# BatteryStackMonitor.net
KiCad netlist of a schematic drawn in Altium Designer
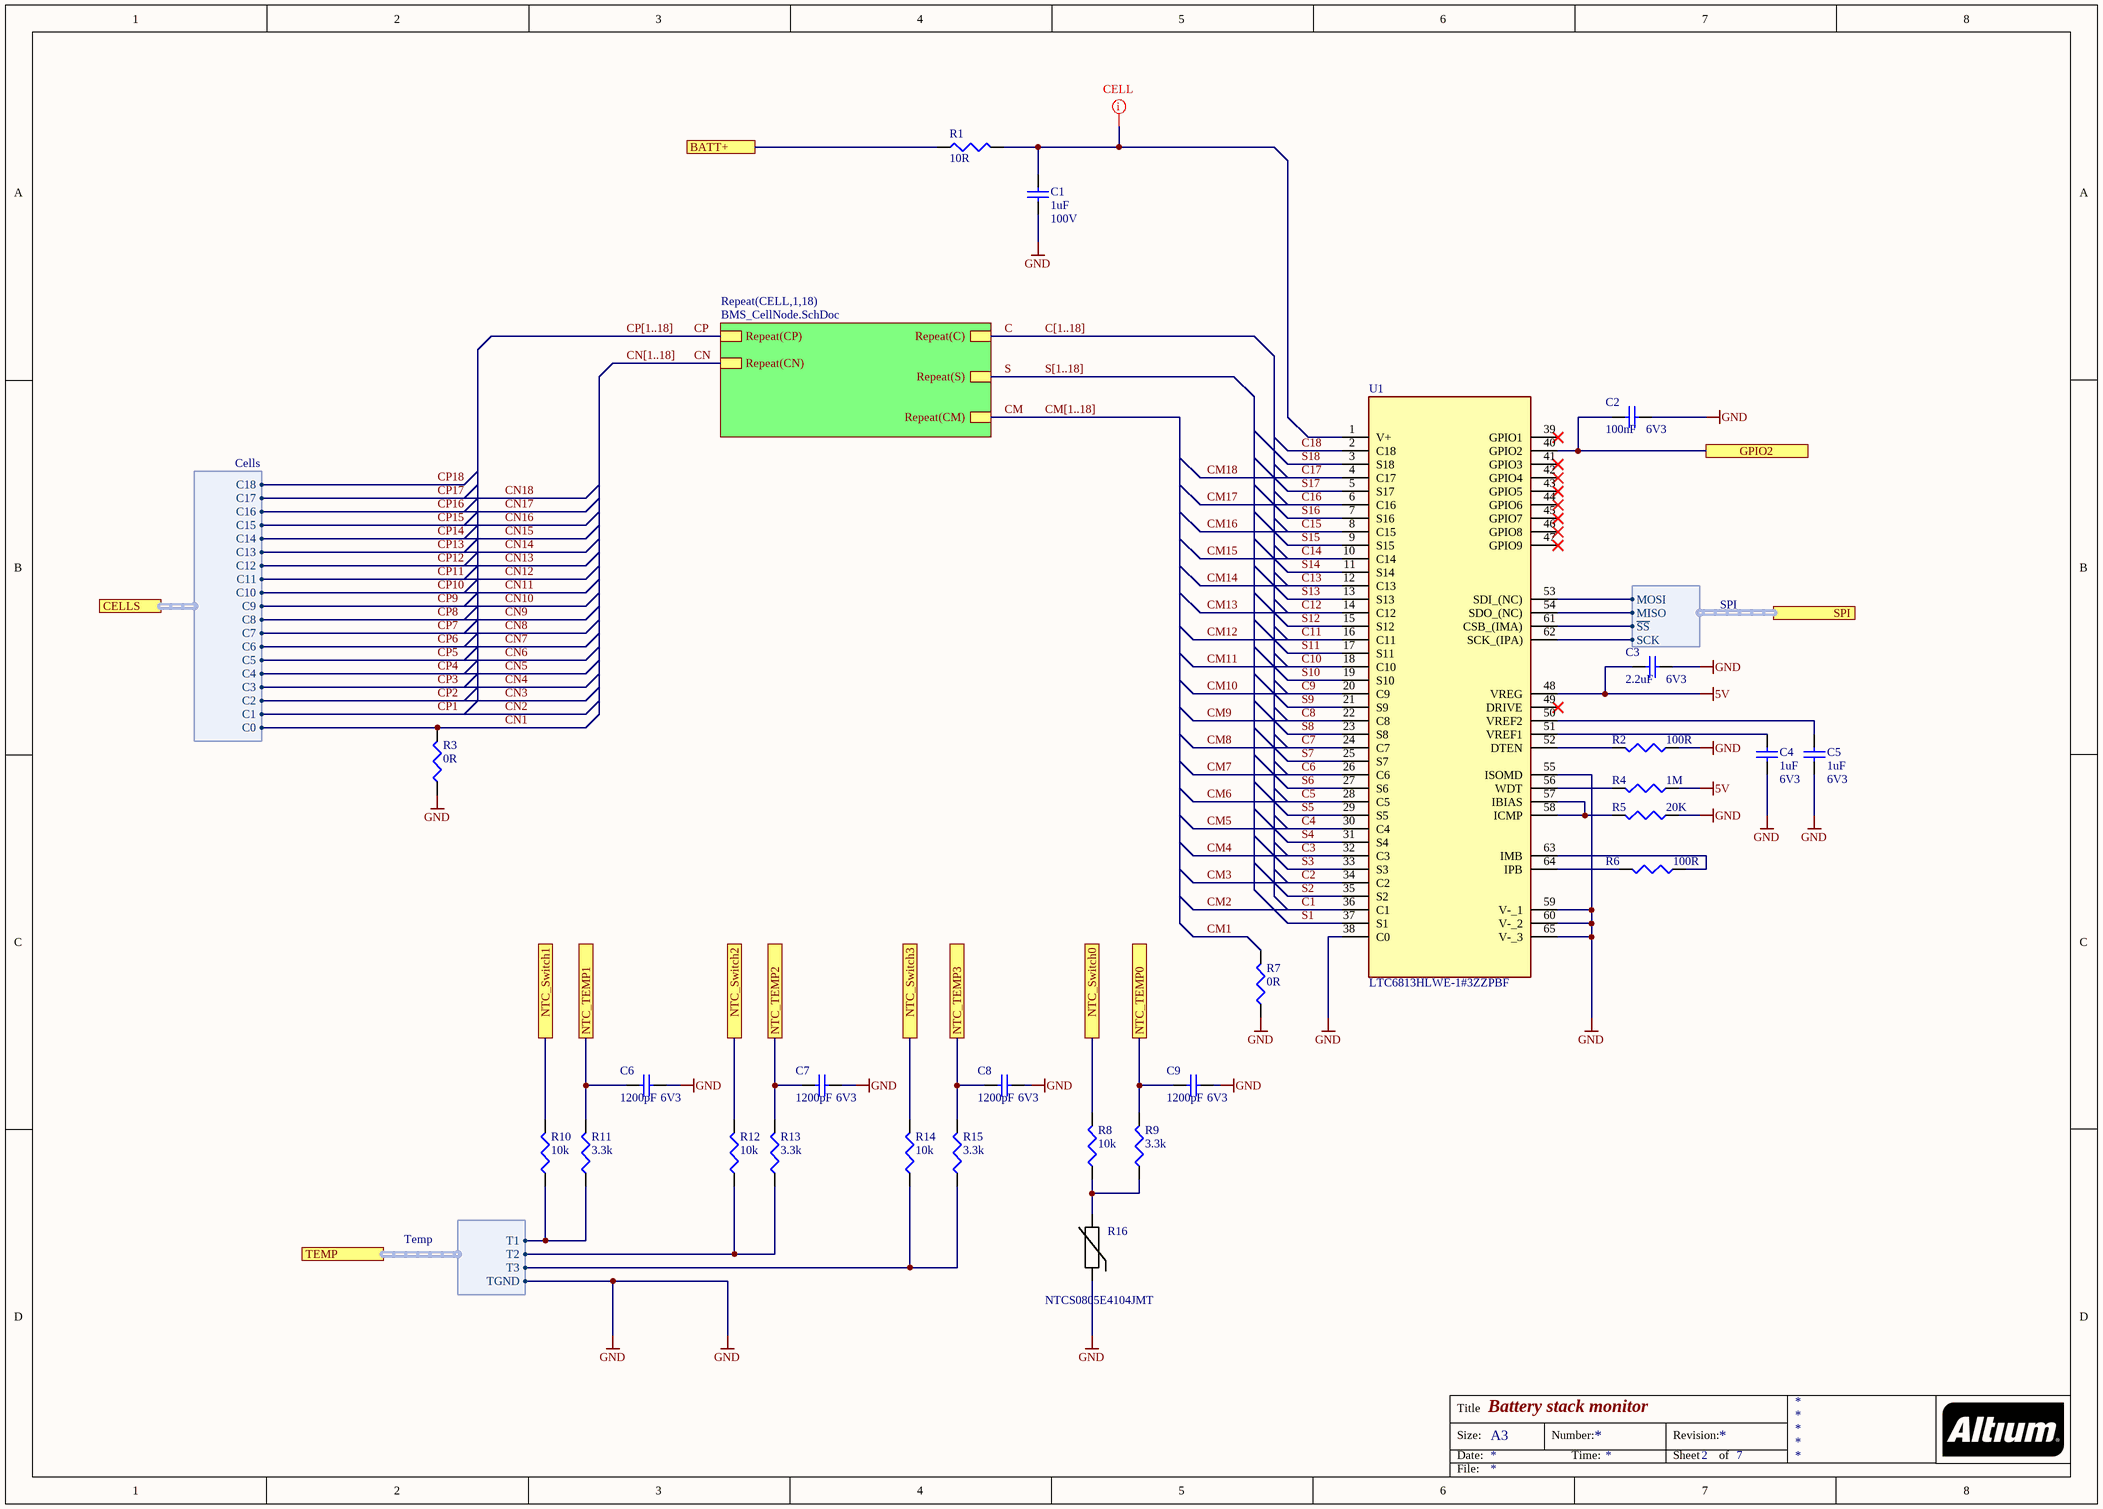
[diagram p0: BatteryStackMonitor.SchDoc]

(export (version "E")
  (design (tool "Eeschema 10.0.6"))
  (components
    (comp (ref "C1")
      (value "1uF")
      (footprint "VESC_BMS:C-1206")
      (description "Capacitor, 1uF, 100V, X7R")
      (fields (field (name "VOLTAGE RATING") "100V"))
      (libsource (lib "AR_Capacitors_Ceramic") (part "1uF/1206/CER/100V"))
    )
    (comp (ref "C2")
      (value "100nF")
      (footprint "VESC_BMS:C0402")
      (description "Capacitor, 1uF, 6.3V, X5R")
      (fields (field (name "VOLTAGE RATING") "6V3"))
      (libsource (lib "AR_Capacitors_Ceramic") (part "1uF/0402/CER/6.3V"))
    )
    (comp (ref "C3")
      (value "2.2uF")
      (footprint "VESC_BMS:C0402")
      (description "Capacitor, 1uF, 6.3V, X5R")
      (fields (field (name "VOLTAGE RATING") "6V3"))
      (libsource (lib "AR_Capacitors_Ceramic") (part "1uF/0402/CER/6.3V"))
    )
    (comp (ref "C4")
      (value "1uF")
      (footprint "VESC_BMS:C0402")
      (description "Capacitor, 1uF, 6.3V, X5R")
      (fields (field (name "VOLTAGE RATING") "6V3"))
      (libsource (lib "AR_Capacitors_Ceramic") (part "1uF/0402/CER/6.3V"))
    )
    (comp (ref "C5")
      (value "1uF")
      (footprint "VESC_BMS:C0402")
      (description "Capacitor, 1uF, 6.3V, X5R")
      (fields (field (name "VOLTAGE RATING") "6V3"))
      (libsource (lib "AR_Capacitors_Ceramic") (part "1uF/0402/CER/6.3V"))
    )
    (comp (ref "C6")
      (value "1200pF")
      (footprint "VESC_BMS:C0402")
      (description "Capacitor, 1uF, 6.3V, X5R")
      (fields (field (name "VOLTAGE RATING") "6V3"))
      (libsource (lib "AR_Capacitors_Ceramic") (part "1uF/0402/CER/6.3V"))
    )
    (comp (ref "C7")
      (value "1200pF")
      (footprint "VESC_BMS:C0402")
      (description "Capacitor, 1uF, 6.3V, X5R")
      (fields (field (name "VOLTAGE RATING") "6V3"))
      (libsource (lib "AR_Capacitors_Ceramic") (part "1uF/0402/CER/6.3V"))
    )
    (comp (ref "C8")
      (value "1200pF")
      (footprint "VESC_BMS:C0402")
      (description "Capacitor, 1uF, 6.3V, X5R")
      (fields (field (name "VOLTAGE RATING") "6V3"))
      (libsource (lib "AR_Capacitors_Ceramic") (part "1uF/0402/CER/6.3V"))
    )
    (comp (ref "C9")
      (value "1200pF")
      (footprint "VESC_BMS:C0402")
      (description "Capacitor, 1uF, 6.3V, X5R")
      (fields (field (name "VOLTAGE RATING") "6V3"))
      (libsource (lib "AR_Capacitors_Ceramic") (part "1uF/0402/CER/6.3V"))
    )
    (comp (ref "R1")
      (value "10R")
      (footprint "R1206")
      (description "Resistor")
      (fields (field (name "MANUFACTURER_PART_NUMBER") "RQ73C2B10RBTDF"))
      (libsource (lib "VESC_BMS") (part "RQ73C2B10RBTDF"))
    )
    (comp (ref "R2")
      (value "100R")
      (footprint "VESC_BMS:0402")
      (description "Resistor, 1M, 0.1%, 0.0625W, 50V, 100PPM, 0402")
      (libsource (lib "AR_Resistors_SMD") (part "1M/0402/0063W/50V"))
    )
    (comp (ref "R3")
      (value "0R")
      (footprint "VESC_BMS:0603")
      (description "Resistor, 0R, 0.1%, 0.063W, 50V, 200PPM, 0603")
      (libsource (lib "AR_Resistors_SMD") (part "0/0603/0063W/50V"))
    )
    (comp (ref "R4")
      (value "1M")
      (footprint "VESC_BMS:0402")
      (description "Resistor, 1M, 0.1%, 0.0625W, 50V, 100PPM, 0402")
      (libsource (lib "AR_Resistors_SMD") (part "1M/0402/0063W/50V"))
    )
    (comp (ref "R5")
      (value "20K")
      (footprint "VESC_BMS:0402")
      (description "Resistor, 1M, 0.1%, 0.0625W, 50V, 100PPM, 0402")
      (libsource (lib "AR_Resistors_SMD") (part "1M/0402/0063W/50V"))
    )
    (comp (ref "R6")
      (value "100R")
      (footprint "VESC_BMS:0402")
      (description "Resistor, 1M, 0.1%, 0.0625W, 50V, 100PPM, 0402")
      (libsource (lib "AR_Resistors_SMD") (part "1M/0402/0063W/50V"))
    )
    (comp (ref "R7")
      (value "0R")
      (footprint "VESC_BMS:0603")
      (description "Resistor, 0R, 0.1%, 0.063W, 50V, 200PPM, 0603")
      (libsource (lib "AR_Resistors_SMD") (part "0/0603/0063W/50V"))
    )
    (comp (ref "R8")
      (value "10k")
      (footprint "VESC_BMS:0402")
      (description "Resistor, 10k, 0.1%, 0.0625W, 50V, 100PPM, 0402")
      (libsource (lib "AR_Resistors_SMD") (part "10k/0402/0063W/50V"))
    )
    (comp (ref "R9")
      (value "3.3k")
      (footprint "VESC_BMS:0402")
      (description "Resistor, 10k, 0.1%, 0.0625W, 50V, 100PPM, 0402")
      (libsource (lib "AR_Resistors_SMD") (part "10k/0402/0063W/50V"))
    )
    (comp (ref "R10")
      (value "10k")
      (footprint "VESC_BMS:0402")
      (description "Resistor, 10k, 0.1%, 0.0625W, 50V, 100PPM, 0402")
      (libsource (lib "AR_Resistors_SMD") (part "10k/0402/0063W/50V"))
    )
    (comp (ref "R11")
      (value "3.3k")
      (footprint "VESC_BMS:0402")
      (description "Resistor, 10k, 0.1%, 0.0625W, 50V, 100PPM, 0402")
      (libsource (lib "AR_Resistors_SMD") (part "10k/0402/0063W/50V"))
    )
    (comp (ref "R12")
      (value "10k")
      (footprint "VESC_BMS:0402")
      (description "Resistor, 10k, 0.1%, 0.0625W, 50V, 100PPM, 0402")
      (libsource (lib "AR_Resistors_SMD") (part "10k/0402/0063W/50V"))
    )
    (comp (ref "R13")
      (value "3.3k")
      (footprint "VESC_BMS:0402")
      (description "Resistor, 10k, 0.1%, 0.0625W, 50V, 100PPM, 0402")
      (libsource (lib "AR_Resistors_SMD") (part "10k/0402/0063W/50V"))
    )
    (comp (ref "R14")
      (value "10k")
      (footprint "VESC_BMS:0402")
      (description "Resistor, 10k, 0.1%, 0.0625W, 50V, 100PPM, 0402")
      (libsource (lib "AR_Resistors_SMD") (part "10k/0402/0063W/50V"))
    )
    (comp (ref "R15")
      (value "3.3k")
      (footprint "VESC_BMS:0402")
      (description "Resistor, 10k, 0.1%, 0.0625W, 50V, 100PPM, 0402")
      (libsource (lib "AR_Resistors_SMD") (part "10k/0402/0063W/50V"))
    )
    (comp (ref "R16")
      (value "NTCS0805E4104JMT")
      (footprint "VESC_BMS:0603")
      (description "THERMISTOR, NTC, 100K, 5%")
      (libsource (lib "VESC_BMS") (part "NTCS0805E4104JMT"))
    )
    (comp (ref "U1")
      (value "LTC6813HLWE-1#3ZZPBF")
      (footprint "VESC_BMS:QFP50P1200X1200X160-65N")
      (description "Integrated Circuit")
      (fields (field (name "MOUSER PART NUMBER") "584-6813HLWE13ZZPBF"))
      (libsource (lib "DB10005_DieBieMS") (part "LTC6813HLWE-1#3ZZPBF"))
    )
  )
  (nets
    (net (code "4") (name "/BATT+") (class "Default")
      (node (ref "R1") (pin "1") (pinfunction "1_1") (pintype "passive"))
    )
    (net (code "6") (name "/C1") (class "Default")
      (node (ref "U1") (pin "36") (pinfunction "C1_36") (pintype "passive"))
    )
    (net (code "7") (name "/C2") (class "Default")
      (node (ref "U1") (pin "34") (pinfunction "C2_34") (pintype "passive"))
    )
    (net (code "8") (name "/C3") (class "Default")
      (node (ref "U1") (pin "32") (pinfunction "C3_32") (pintype "passive"))
    )
    (net (code "9") (name "/C4") (class "Default")
      (node (ref "U1") (pin "30") (pinfunction "C4_30") (pintype "passive"))
    )
    (net (code "10") (name "/C5") (class "Default")
      (node (ref "U1") (pin "28") (pinfunction "C5_28") (pintype "passive"))
    )
    (net (code "11") (name "/C6") (class "Default")
      (node (ref "U1") (pin "26") (pinfunction "C6_26") (pintype "passive"))
    )
    (net (code "12") (name "/C7") (class "Default")
      (node (ref "U1") (pin "24") (pinfunction "C7_24") (pintype "passive"))
    )
    (net (code "13") (name "/C8") (class "Default")
      (node (ref "U1") (pin "22") (pinfunction "C8_22") (pintype "passive"))
    )
    (net (code "14") (name "/C9") (class "Default")
      (node (ref "U1") (pin "20") (pinfunction "C9_20") (pintype "passive"))
    )
    (net (code "15") (name "/C10") (class "Default")
      (node (ref "U1") (pin "18") (pinfunction "C10_18") (pintype "passive"))
    )
    (net (code "16") (name "/C11") (class "Default")
      (node (ref "U1") (pin "16") (pinfunction "C11_16") (pintype "passive"))
    )
    (net (code "17") (name "/C12") (class "Default")
      (node (ref "U1") (pin "14") (pinfunction "C12_14") (pintype "passive"))
    )
    (net (code "18") (name "/C13") (class "Default")
      (node (ref "U1") (pin "12") (pinfunction "C13_12") (pintype "passive"))
    )
    (net (code "19") (name "/C14") (class "Default")
      (node (ref "U1") (pin "10") (pinfunction "C14_10") (pintype "passive"))
    )
    (net (code "20") (name "/C15") (class "Default")
      (node (ref "U1") (pin "8") (pinfunction "C15_8") (pintype "passive"))
    )
    (net (code "21") (name "/C16") (class "Default")
      (node (ref "U1") (pin "6") (pinfunction "C16_6") (pintype "passive"))
    )
    (net (code "22") (name "/C17") (class "Default")
      (node (ref "U1") (pin "4") (pinfunction "C17_4") (pintype "passive"))
    )
    (net (code "23") (name "/C18") (class "Default")
      (node (ref "U1") (pin "2") (pinfunction "C18_2") (pintype "passive"))
    )
    (net (code "25") (name "/CM1") (class "Default")
      (node (ref "R7") (pin "2") (pinfunction "2_2") (pintype "passive"))
    )
    (net (code "28") (name "/CN1") (class "Default")
      (node (ref "R3") (pin "2") (pinfunction "2_2") (pintype "passive"))
    )
    (net (code "51") (name "/GPIO2") (class "Default")
      (node (ref "C2") (pin "1") (pinfunction "1_1") (pintype "passive"))
      (node (ref "U1") (pin "40") (pinfunction "GPIO2_40") (pintype "passive"))
    )
    (net (code "52") (name "/NTC_Switch0") (class "Default")
      (node (ref "R8") (pin "2") (pinfunction "2_2") (pintype "passive"))
    )
    (net (code "53") (name "/NTC_Switch1") (class "Default")
      (node (ref "R10") (pin "2") (pinfunction "2_2") (pintype "passive"))
    )
    (net (code "54") (name "/NTC_Switch2") (class "Default")
      (node (ref "R12") (pin "2") (pinfunction "2_2") (pintype "passive"))
    )
    (net (code "55") (name "/NTC_Switch3") (class "Default")
      (node (ref "R14") (pin "2") (pinfunction "2_2") (pintype "passive"))
    )
    (net (code "56") (name "/NTC_TEMP0") (class "Default")
      (node (ref "C9") (pin "1") (pinfunction "1_1") (pintype "passive"))
      (node (ref "R9") (pin "2") (pinfunction "2_2") (pintype "passive"))
    )
    (net (code "57") (name "/NTC_TEMP1") (class "Default")
      (node (ref "C6") (pin "1") (pinfunction "1_1") (pintype "passive"))
      (node (ref "R11") (pin "2") (pinfunction "2_2") (pintype "passive"))
    )
    (net (code "58") (name "/NTC_TEMP2") (class "Default")
      (node (ref "C7") (pin "1") (pinfunction "1_1") (pintype "passive"))
      (node (ref "R13") (pin "2") (pinfunction "2_2") (pintype "passive"))
    )
    (net (code "59") (name "/NTC_TEMP3") (class "Default")
      (node (ref "C8") (pin "1") (pinfunction "1_1") (pintype "passive"))
      (node (ref "R15") (pin "2") (pinfunction "2_2") (pintype "passive"))
    )
    (net (code "61") (name "/S1") (class "Default")
      (node (ref "U1") (pin "37") (pinfunction "S1_37") (pintype "passive"))
    )
    (net (code "62") (name "/S2") (class "Default")
      (node (ref "U1") (pin "35") (pinfunction "S2_35") (pintype "passive"))
    )
    (net (code "63") (name "/S3") (class "Default")
      (node (ref "U1") (pin "33") (pinfunction "S3_33") (pintype "passive"))
    )
    (net (code "64") (name "/S4") (class "Default")
      (node (ref "U1") (pin "31") (pinfunction "S4_31") (pintype "passive"))
    )
    (net (code "65") (name "/S5") (class "Default")
      (node (ref "U1") (pin "29") (pinfunction "S5_29") (pintype "passive"))
    )
    (net (code "66") (name "/S6") (class "Default")
      (node (ref "U1") (pin "27") (pinfunction "S6_27") (pintype "passive"))
    )
    (net (code "67") (name "/S7") (class "Default")
      (node (ref "U1") (pin "25") (pinfunction "S7_25") (pintype "passive"))
    )
    (net (code "68") (name "/S8") (class "Default")
      (node (ref "U1") (pin "23") (pinfunction "S8_23") (pintype "passive"))
    )
    (net (code "69") (name "/S9") (class "Default")
      (node (ref "U1") (pin "21") (pinfunction "S9_21") (pintype "passive"))
    )
    (net (code "70") (name "/S10") (class "Default")
      (node (ref "U1") (pin "19") (pinfunction "S10_19") (pintype "passive"))
    )
    (net (code "71") (name "/S11") (class "Default")
      (node (ref "U1") (pin "17") (pinfunction "S11_17") (pintype "passive"))
    )
    (net (code "72") (name "/S12") (class "Default")
      (node (ref "U1") (pin "15") (pinfunction "S12_15") (pintype "passive"))
    )
    (net (code "73") (name "/S13") (class "Default")
      (node (ref "U1") (pin "13") (pinfunction "S13_13") (pintype "passive"))
    )
    (net (code "74") (name "/S14") (class "Default")
      (node (ref "U1") (pin "11") (pinfunction "S14_11") (pintype "passive"))
    )
    (net (code "75") (name "/S15") (class "Default")
      (node (ref "U1") (pin "9") (pinfunction "S15_9") (pintype "passive"))
    )
    (net (code "76") (name "/S16") (class "Default")
      (node (ref "U1") (pin "7") (pinfunction "S16_7") (pintype "passive"))
    )
    (net (code "77") (name "/S17") (class "Default")
      (node (ref "U1") (pin "5") (pinfunction "S17_5") (pintype "passive"))
    )
    (net (code "78") (name "/S18") (class "Default")
      (node (ref "U1") (pin "3") (pinfunction "S18_3") (pintype "passive"))
    )
    (net (code "83") (name "5V") (class "Default")
      (node (ref "C3") (pin "1") (pinfunction "1_1") (pintype "passive"))
      (node (ref "R4") (pin "1") (pinfunction "1_1") (pintype "passive"))
      (node (ref "U1") (pin "48") (pinfunction "VREG_48") (pintype "passive"))
    )
    (net (code "84") (name "GND") (class "Default")
      (node (ref "C1") (pin "1") (pinfunction "1_1") (pintype "passive"))
      (node (ref "C2") (pin "2") (pinfunction "2_2") (pintype "passive"))
      (node (ref "C3") (pin "2") (pinfunction "2_2") (pintype "passive"))
      (node (ref "C4") (pin "2") (pinfunction "2_2") (pintype "passive"))
      (node (ref "C5") (pin "2") (pinfunction "2_2") (pintype "passive"))
      (node (ref "C6") (pin "2") (pinfunction "2_2") (pintype "passive"))
      (node (ref "C7") (pin "2") (pinfunction "2_2") (pintype "passive"))
      (node (ref "C8") (pin "2") (pinfunction "2_2") (pintype "passive"))
      (node (ref "C9") (pin "2") (pinfunction "2_2") (pintype "passive"))
      (node (ref "R16") (pin "1") (pinfunction "1_1") (pintype "passive"))
      (node (ref "R2") (pin "1") (pinfunction "1_1") (pintype "passive"))
      (node (ref "R3") (pin "1") (pinfunction "1_1") (pintype "passive"))
      (node (ref "R5") (pin "1") (pinfunction "1_1") (pintype "passive"))
      (node (ref "R7") (pin "1") (pinfunction "1_1") (pintype "passive"))
      (node (ref "U1") (pin "38") (pinfunction "C0_38") (pintype "passive"))
      (node (ref "U1") (pin "55") (pinfunction "ISOMD_55") (pintype "passive"))
      (node (ref "U1") (pin "59") (pinfunction "V-_1_59") (pintype "passive"))
      (node (ref "U1") (pin "60") (pinfunction "V-_2_60") (pintype "passive"))
      (node (ref "U1") (pin "65") (pinfunction "V-_3_65") (pintype "passive"))
    )
    (net (code "85") (name "Net-(R10-Pad1)") (class "Default")
      (node (ref "R10") (pin "1") (pinfunction "1_1") (pintype "passive"))
      (node (ref "R11") (pin "1") (pinfunction "1_1") (pintype "passive"))
    )
    (net (code "86") (name "Net-(R12-Pad1)") (class "Default")
      (node (ref "R12") (pin "1") (pinfunction "1_1") (pintype "passive"))
      (node (ref "R13") (pin "1") (pinfunction "1_1") (pintype "passive"))
    )
    (net (code "87") (name "Net-(R14-Pad1)") (class "Default")
      (node (ref "R14") (pin "1") (pinfunction "1_1") (pintype "passive"))
      (node (ref "R15") (pin "1") (pinfunction "1_1") (pintype "passive"))
    )
    (net (code "88") (name "Net-(R16-Pad2)") (class "Default")
      (node (ref "R16") (pin "2") (pinfunction "2_2") (pintype "passive"))
      (node (ref "R8") (pin "1") (pinfunction "1_1") (pintype "passive"))
      (node (ref "R9") (pin "1") (pinfunction "1_1") (pintype "passive"))
    )
    (net (code "89") (name "Net-(U1-DTEN)") (class "Default")
      (node (ref "R2") (pin "2") (pinfunction "2_2") (pintype "passive"))
      (node (ref "U1") (pin "52") (pinfunction "DTEN_52") (pintype "passive"))
    )
    (net (code "90") (name "Net-(U1-IBIAS)") (class "Default")
      (node (ref "R5") (pin "2") (pinfunction "2_2") (pintype "passive"))
      (node (ref "U1") (pin "57") (pinfunction "IBIAS_57") (pintype "passive"))
      (node (ref "U1") (pin "58") (pinfunction "ICMP_58") (pintype "passive"))
    )
    (net (code "91") (name "Net-(U1-IMB)") (class "Default")
      (node (ref "R6") (pin "1") (pinfunction "1_1") (pintype "passive"))
      (node (ref "U1") (pin "63") (pinfunction "IMB_63") (pintype "passive"))
    )
    (net (code "92") (name "Net-(U1-IPB)") (class "Default")
      (node (ref "R6") (pin "2") (pinfunction "2_2") (pintype "passive"))
      (node (ref "U1") (pin "64") (pinfunction "IPB_64") (pintype "passive"))
    )
    (net (code "93") (name "Net-(U1-V+)") (class "Default")
      (node (ref "C1") (pin "2") (pinfunction "2_2") (pintype "passive"))
      (node (ref "R1") (pin "2") (pinfunction "2_2") (pintype "passive"))
      (node (ref "U1") (pin "1") (pinfunction "V+_1") (pintype "passive"))
    )
    (net (code "94") (name "Net-(U1-VREF1)") (class "Default")
      (node (ref "C4") (pin "1") (pinfunction "1_1") (pintype "passive"))
      (node (ref "U1") (pin "51") (pinfunction "VREF1_51") (pintype "passive"))
    )
    (net (code "95") (name "Net-(U1-VREF2)") (class "Default")
      (node (ref "C5") (pin "1") (pinfunction "1_1") (pintype "passive"))
      (node (ref "U1") (pin "50") (pinfunction "VREF2_50") (pintype "passive"))
    )
    (net (code "96") (name "Net-(U1-WDT)") (class "Default")
      (node (ref "R4") (pin "2") (pinfunction "2_2") (pintype "passive"))
      (node (ref "U1") (pin "56") (pinfunction "WDT_56") (pintype "passive"))
    )
    (net (code "97") (name "unconnected-(U1-CSB_(IMA)-Pad61)") (class "Default")
      (node (ref "U1") (pin "61") (pinfunction "CSB_(IMA)_61") (pintype "passive"))
    )
    (net (code "98") (name "unconnected-(U1-DRIVE-Pad49)") (class "Default")
      (node (ref "U1") (pin "49") (pinfunction "DRIVE_49") (pintype "passive+no_connect"))
    )
    (net (code "99") (name "unconnected-(U1-GPIO1-Pad39)") (class "Default")
      (node (ref "U1") (pin "39") (pinfunction "GPIO1_39") (pintype "passive+no_connect"))
    )
    (net (code "100") (name "unconnected-(U1-GPIO3-Pad41)") (class "Default")
      (node (ref "U1") (pin "41") (pinfunction "GPIO3_41") (pintype "passive+no_connect"))
    )
    (net (code "101") (name "unconnected-(U1-GPIO4-Pad42)") (class "Default")
      (node (ref "U1") (pin "42") (pinfunction "GPIO4_42") (pintype "passive+no_connect"))
    )
    (net (code "102") (name "unconnected-(U1-GPIO5-Pad43)") (class "Default")
      (node (ref "U1") (pin "43") (pinfunction "GPIO5_43") (pintype "passive+no_connect"))
    )
    (net (code "103") (name "unconnected-(U1-GPIO6-Pad44)") (class "Default")
      (node (ref "U1") (pin "44") (pinfunction "GPIO6_44") (pintype "passive+no_connect"))
    )
    (net (code "104") (name "unconnected-(U1-GPIO7-Pad45)") (class "Default")
      (node (ref "U1") (pin "45") (pinfunction "GPIO7_45") (pintype "passive+no_connect"))
    )
    (net (code "105") (name "unconnected-(U1-GPIO8-Pad46)") (class "Default")
      (node (ref "U1") (pin "46") (pinfunction "GPIO8_46") (pintype "passive+no_connect"))
    )
    (net (code "106") (name "unconnected-(U1-GPIO9-Pad47)") (class "Default")
      (node (ref "U1") (pin "47") (pinfunction "GPIO9_47") (pintype "passive+no_connect"))
    )
    (net (code "107") (name "unconnected-(U1-SCK_(IPA)-Pad62)") (class "Default")
      (node (ref "U1") (pin "62") (pinfunction "SCK_(IPA)_62") (pintype "passive"))
    )
    (net (code "108") (name "unconnected-(U1-SDI_(NC)-Pad53)") (class "Default")
      (node (ref "U1") (pin "53") (pinfunction "SDI_(NC)_53") (pintype "passive"))
    )
    (net (code "109") (name "unconnected-(U1-SDO_(NC)-Pad54)") (class "Default")
      (node (ref "U1") (pin "54") (pinfunction "SDO_(NC)_54") (pintype "passive"))
    )
  )
)
